# 2_byte_output.net
KiCad netlist of a schematic drawn in EAGLE
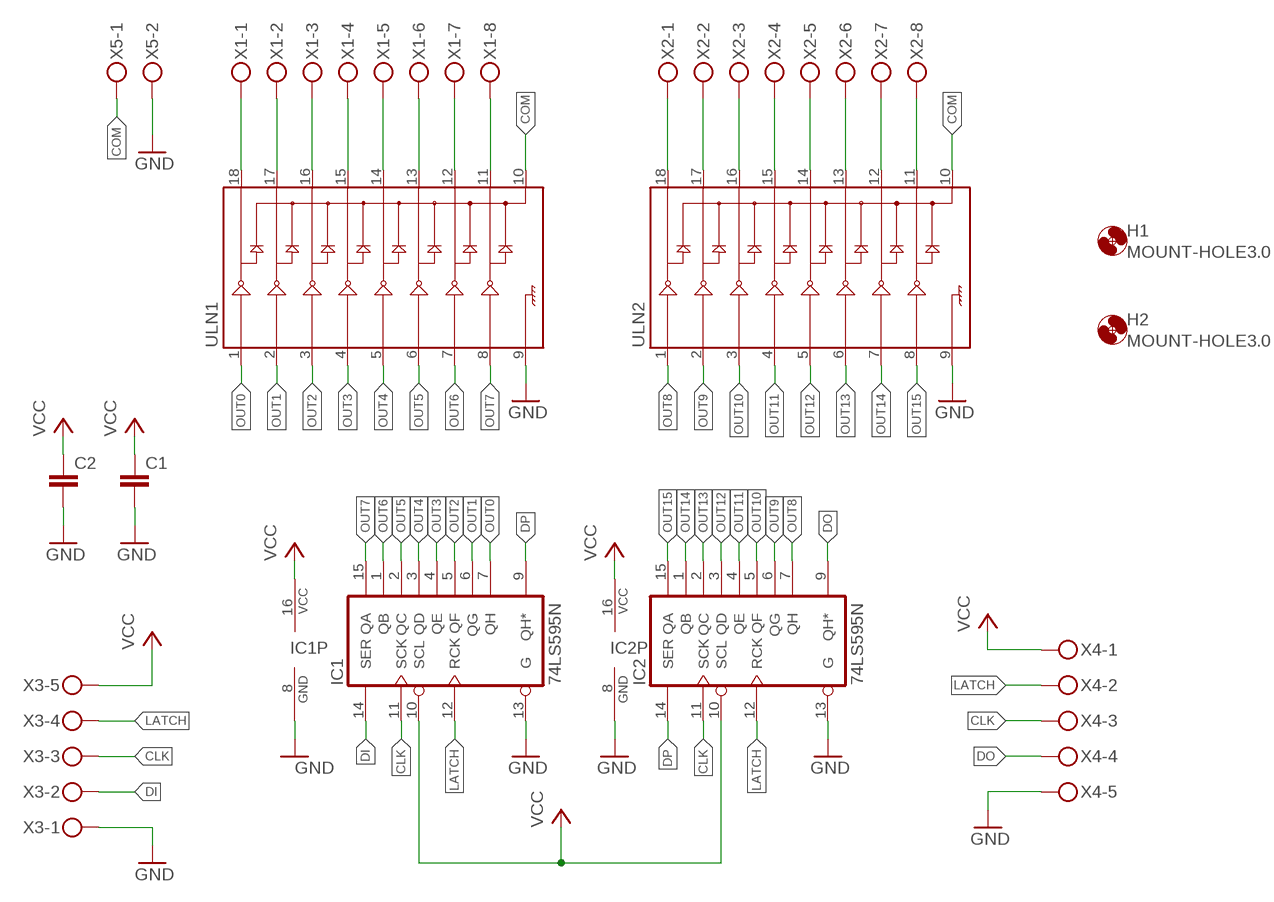
[diagram p0: schematic, sheet 1]

(export (version "E")
  (design (tool "Eeschema 10.0.6"))
  (components
    (comp (ref "C1")
      (value "C-EU050-035X075")
      (footprint "eagle-import:C050-035X075")
      (libsource (lib "eagle-import") (part "C-EU050-035X075"))
    )
    (comp (ref "C2")
      (value "C-EU050-035X075")
      (footprint "eagle-import:C050-035X075")
      (libsource (lib "eagle-import") (part "C-EU050-035X075"))
    )
    (comp (ref "H1")
      (value "MOUNT-HOLE3.0")
      (footprint "eagle-import:3,0")
      (libsource (lib "eagle-import") (part "MOUNT-HOLE3.0"))
    )
    (comp (ref "H2")
      (value "MOUNT-HOLE3.0")
      (footprint "eagle-import:3,0")
      (libsource (lib "eagle-import") (part "MOUNT-HOLE3.0"))
    )
    (comp (ref "IC1")
      (value "74LS595N")
      (footprint "eagle-import:DIL16")
      (libsource (lib "eagle-import") (part "74595NLS"))
    )
    (comp (ref "IC2")
      (value "74LS595N")
      (footprint "eagle-import:DIL16")
      (libsource (lib "eagle-import") (part "74595NLS"))
    )
    (comp (ref "ULN1")
      (value "ULN2803DIP")
      (footprint "eagle-import:DIL18")
      (libsource (lib "eagle-import") (part "ULN2803DIP"))
    )
    (comp (ref "ULN2")
      (value "ULN2803DIP")
      (footprint "eagle-import:DIL18")
      (libsource (lib "eagle-import") (part "ULN2803DIP"))
    )
    (comp (ref "X1")
      (value "MKDSN1,5/8-5,08")
      (footprint "eagle-import:MKDSN1,5_8-5,08")
      (libsource (lib "eagle-import") (part "MKDSN1,5/8-5,08"))
    )
    (comp (ref "X2")
      (value "MKDSN1,5/8-5,08")
      (footprint "eagle-import:MKDSN1,5_8-5,08")
      (libsource (lib "eagle-import") (part "MKDSN1,5/8-5,08"))
    )
    (comp (ref "X3")
      (value "MKDSN1,5/5-5,08")
      (footprint "eagle-import:MKDSN1,5_5-5,08")
      (libsource (lib "eagle-import") (part "MKDSN1,5/5-5,08"))
    )
    (comp (ref "X4")
      (value "MKDSN1,5/5-5,08")
      (footprint "eagle-import:MKDSN1,5_5-5,08")
      (libsource (lib "eagle-import") (part "MKDSN1,5/5-5,08"))
    )
    (comp (ref "X5")
      (value "MKDSN1,5/2-5,08")
      (footprint "eagle-import:MKDSN1,5_2-5,08")
      (libsource (lib "eagle-import") (part "MKDSN1,5/2-5,08"))
    )
  )
  (nets
    (net (code "1") (name "CLK") (class "Default")
      (node (ref "IC1") (pin "11") (pinfunction "SCK_11") (pintype "input"))
      (node (ref "IC2") (pin "11") (pinfunction "SCK_11") (pintype "input"))
      (node (ref "X3") (pin "3") (pinfunction "KL_3") (pintype "passive"))
      (node (ref "X4") (pin "3") (pinfunction "KL_3") (pintype "passive"))
    )
    (net (code "2") (name "COM") (class "Default")
      (node (ref "ULN1") (pin "10") (pinfunction "10_10") (pintype "bidirectional"))
      (node (ref "ULN2") (pin "10") (pinfunction "10_10") (pintype "bidirectional"))
      (node (ref "X5") (pin "1") (pinfunction "KL_1") (pintype "passive"))
    )
    (net (code "3") (name "DI") (class "Default")
      (node (ref "IC1") (pin "14") (pinfunction "SER_14") (pintype "input"))
      (node (ref "X3") (pin "2") (pinfunction "KL_2") (pintype "passive"))
    )
    (net (code "4") (name "DO") (class "Default")
      (node (ref "IC2") (pin "9") (pinfunction "QH*_9") (pintype "tri_state"))
      (node (ref "X4") (pin "4") (pinfunction "KL_4") (pintype "passive"))
    )
    (net (code "5") (name "DP") (class "Default")
      (node (ref "IC1") (pin "9") (pinfunction "QH*_9") (pintype "tri_state"))
      (node (ref "IC2") (pin "14") (pinfunction "SER_14") (pintype "input"))
    )
    (net (code "6") (name "GND") (class "Default")
      (node (ref "C1") (pin "2") (pinfunction "2_2") (pintype "passive"))
      (node (ref "C2") (pin "2") (pinfunction "2_2") (pintype "passive"))
      (node (ref "IC1") (pin "13") (pinfunction "G_13") (pintype "input"))
      (node (ref "IC1") (pin "8") (pinfunction "GND_8") (pintype "power_in"))
      (node (ref "IC2") (pin "13") (pinfunction "G_13") (pintype "input"))
      (node (ref "IC2") (pin "8") (pinfunction "GND_8") (pintype "power_in"))
      (node (ref "ULN1") (pin "9") (pinfunction "9_9") (pintype "bidirectional"))
      (node (ref "ULN2") (pin "9") (pinfunction "9_9") (pintype "bidirectional"))
      (node (ref "X3") (pin "1") (pinfunction "KL_1") (pintype "passive"))
      (node (ref "X4") (pin "5") (pinfunction "KL_5") (pintype "passive"))
      (node (ref "X5") (pin "2") (pinfunction "KL_2") (pintype "passive"))
    )
    (net (code "7") (name "LATCH") (class "Default")
      (node (ref "IC1") (pin "12") (pinfunction "RCK_12") (pintype "input"))
      (node (ref "IC2") (pin "12") (pinfunction "RCK_12") (pintype "input"))
      (node (ref "X3") (pin "4") (pinfunction "KL_4") (pintype "passive"))
      (node (ref "X4") (pin "2") (pinfunction "KL_2") (pintype "passive"))
    )
    (net (code "8") (name "Net-(X1A-KL)") (class "Default")
      (node (ref "ULN1") (pin "18") (pinfunction "18_18") (pintype "bidirectional"))
      (node (ref "X1") (pin "1") (pinfunction "KL_1") (pintype "passive"))
    )
    (net (code "9") (name "Net-(X1B-KL)") (class "Default")
      (node (ref "ULN1") (pin "17") (pinfunction "17_17") (pintype "bidirectional"))
      (node (ref "X1") (pin "2") (pinfunction "KL_2") (pintype "passive"))
    )
    (net (code "10") (name "Net-(X1C-KL)") (class "Default")
      (node (ref "ULN1") (pin "16") (pinfunction "16_16") (pintype "bidirectional"))
      (node (ref "X1") (pin "3") (pinfunction "KL_3") (pintype "passive"))
    )
    (net (code "11") (name "Net-(X1D-KL)") (class "Default")
      (node (ref "ULN1") (pin "15") (pinfunction "15_15") (pintype "bidirectional"))
      (node (ref "X1") (pin "4") (pinfunction "KL_4") (pintype "passive"))
    )
    (net (code "12") (name "Net-(X1E-KL)") (class "Default")
      (node (ref "ULN1") (pin "14") (pinfunction "14_14") (pintype "bidirectional"))
      (node (ref "X1") (pin "5") (pinfunction "KL_5") (pintype "passive"))
    )
    (net (code "13") (name "Net-(X1F-KL)") (class "Default")
      (node (ref "ULN1") (pin "13") (pinfunction "13_13") (pintype "bidirectional"))
      (node (ref "X1") (pin "6") (pinfunction "KL_6") (pintype "passive"))
    )
    (net (code "14") (name "Net-(X1G-KL)") (class "Default")
      (node (ref "ULN1") (pin "12") (pinfunction "12_12") (pintype "bidirectional"))
      (node (ref "X1") (pin "7") (pinfunction "KL_7") (pintype "passive"))
    )
    (net (code "15") (name "Net-(X1H-KL)") (class "Default")
      (node (ref "ULN1") (pin "11") (pinfunction "11_11") (pintype "bidirectional"))
      (node (ref "X1") (pin "8") (pinfunction "KL_8") (pintype "passive"))
    )
    (net (code "16") (name "Net-(X2A-KL)") (class "Default")
      (node (ref "ULN2") (pin "18") (pinfunction "18_18") (pintype "bidirectional"))
      (node (ref "X2") (pin "1") (pinfunction "KL_1") (pintype "passive"))
    )
    (net (code "17") (name "Net-(X2B-KL)") (class "Default")
      (node (ref "ULN2") (pin "17") (pinfunction "17_17") (pintype "bidirectional"))
      (node (ref "X2") (pin "2") (pinfunction "KL_2") (pintype "passive"))
    )
    (net (code "18") (name "Net-(X2C-KL)") (class "Default")
      (node (ref "ULN2") (pin "16") (pinfunction "16_16") (pintype "bidirectional"))
      (node (ref "X2") (pin "3") (pinfunction "KL_3") (pintype "passive"))
    )
    (net (code "19") (name "Net-(X2D-KL)") (class "Default")
      (node (ref "ULN2") (pin "15") (pinfunction "15_15") (pintype "bidirectional"))
      (node (ref "X2") (pin "4") (pinfunction "KL_4") (pintype "passive"))
    )
    (net (code "20") (name "Net-(X2E-KL)") (class "Default")
      (node (ref "ULN2") (pin "14") (pinfunction "14_14") (pintype "bidirectional"))
      (node (ref "X2") (pin "5") (pinfunction "KL_5") (pintype "passive"))
    )
    (net (code "21") (name "Net-(X2F-KL)") (class "Default")
      (node (ref "ULN2") (pin "13") (pinfunction "13_13") (pintype "bidirectional"))
      (node (ref "X2") (pin "6") (pinfunction "KL_6") (pintype "passive"))
    )
    (net (code "22") (name "Net-(X2G-KL)") (class "Default")
      (node (ref "ULN2") (pin "12") (pinfunction "12_12") (pintype "bidirectional"))
      (node (ref "X2") (pin "7") (pinfunction "KL_7") (pintype "passive"))
    )
    (net (code "23") (name "Net-(X2H-KL)") (class "Default")
      (node (ref "ULN2") (pin "11") (pinfunction "11_11") (pintype "bidirectional"))
      (node (ref "X2") (pin "8") (pinfunction "KL_8") (pintype "passive"))
    )
    (net (code "24") (name "OUT0") (class "Default")
      (node (ref "IC1") (pin "7") (pinfunction "QH_7") (pintype "tri_state"))
      (node (ref "ULN1") (pin "1") (pinfunction "1_1") (pintype "bidirectional"))
    )
    (net (code "25") (name "OUT1") (class "Default")
      (node (ref "IC1") (pin "6") (pinfunction "QG_6") (pintype "tri_state"))
      (node (ref "ULN1") (pin "2") (pinfunction "2_2") (pintype "bidirectional"))
    )
    (net (code "26") (name "OUT2") (class "Default")
      (node (ref "IC1") (pin "5") (pinfunction "QF_5") (pintype "tri_state"))
      (node (ref "ULN1") (pin "3") (pinfunction "3_3") (pintype "bidirectional"))
    )
    (net (code "27") (name "OUT3") (class "Default")
      (node (ref "IC1") (pin "4") (pinfunction "QE_4") (pintype "tri_state"))
      (node (ref "ULN1") (pin "4") (pinfunction "4_4") (pintype "bidirectional"))
    )
    (net (code "28") (name "OUT4") (class "Default")
      (node (ref "IC1") (pin "3") (pinfunction "QD_3") (pintype "tri_state"))
      (node (ref "ULN1") (pin "5") (pinfunction "5_5") (pintype "bidirectional"))
    )
    (net (code "29") (name "OUT5") (class "Default")
      (node (ref "IC1") (pin "2") (pinfunction "QC_2") (pintype "tri_state"))
      (node (ref "ULN1") (pin "6") (pinfunction "6_6") (pintype "bidirectional"))
    )
    (net (code "30") (name "OUT6") (class "Default")
      (node (ref "IC1") (pin "1") (pinfunction "QB_1") (pintype "tri_state"))
      (node (ref "ULN1") (pin "7") (pinfunction "7_7") (pintype "bidirectional"))
    )
    (net (code "31") (name "OUT7") (class "Default")
      (node (ref "IC1") (pin "15") (pinfunction "QA_15") (pintype "tri_state"))
      (node (ref "ULN1") (pin "8") (pinfunction "8_8") (pintype "bidirectional"))
    )
    (net (code "32") (name "OUT8") (class "Default")
      (node (ref "IC2") (pin "7") (pinfunction "QH_7") (pintype "tri_state"))
      (node (ref "ULN2") (pin "1") (pinfunction "1_1") (pintype "bidirectional"))
    )
    (net (code "33") (name "OUT9") (class "Default")
      (node (ref "IC2") (pin "6") (pinfunction "QG_6") (pintype "tri_state"))
      (node (ref "ULN2") (pin "2") (pinfunction "2_2") (pintype "bidirectional"))
    )
    (net (code "34") (name "OUT10") (class "Default")
      (node (ref "IC2") (pin "5") (pinfunction "QF_5") (pintype "tri_state"))
      (node (ref "ULN2") (pin "3") (pinfunction "3_3") (pintype "bidirectional"))
    )
    (net (code "35") (name "OUT11") (class "Default")
      (node (ref "IC2") (pin "4") (pinfunction "QE_4") (pintype "tri_state"))
      (node (ref "ULN2") (pin "4") (pinfunction "4_4") (pintype "bidirectional"))
    )
    (net (code "36") (name "OUT12") (class "Default")
      (node (ref "IC2") (pin "3") (pinfunction "QD_3") (pintype "tri_state"))
      (node (ref "ULN2") (pin "5") (pinfunction "5_5") (pintype "bidirectional"))
    )
    (net (code "37") (name "OUT13") (class "Default")
      (node (ref "IC2") (pin "2") (pinfunction "QC_2") (pintype "tri_state"))
      (node (ref "ULN2") (pin "6") (pinfunction "6_6") (pintype "bidirectional"))
    )
    (net (code "38") (name "OUT14") (class "Default")
      (node (ref "IC2") (pin "1") (pinfunction "QB_1") (pintype "tri_state"))
      (node (ref "ULN2") (pin "7") (pinfunction "7_7") (pintype "bidirectional"))
    )
    (net (code "39") (name "OUT15") (class "Default")
      (node (ref "IC2") (pin "15") (pinfunction "QA_15") (pintype "tri_state"))
      (node (ref "ULN2") (pin "8") (pinfunction "8_8") (pintype "bidirectional"))
    )
    (net (code "40") (name "VCC") (class "Default")
      (node (ref "C1") (pin "1") (pinfunction "1_1") (pintype "passive"))
      (node (ref "C2") (pin "1") (pinfunction "1_1") (pintype "passive"))
      (node (ref "IC1") (pin "10") (pinfunction "SCL_10") (pintype "input"))
      (node (ref "IC1") (pin "16") (pinfunction "VCC_16") (pintype "power_in"))
      (node (ref "IC2") (pin "10") (pinfunction "SCL_10") (pintype "input"))
      (node (ref "IC2") (pin "16") (pinfunction "VCC_16") (pintype "power_in"))
      (node (ref "X3") (pin "5") (pinfunction "KL_5") (pintype "passive"))
      (node (ref "X4") (pin "1") (pinfunction "KL_1") (pintype "passive"))
    )
  )
)
